# obc-v2_OUT-eMMC.net
KiCad netlist of a schematic drawn in Altium Designer
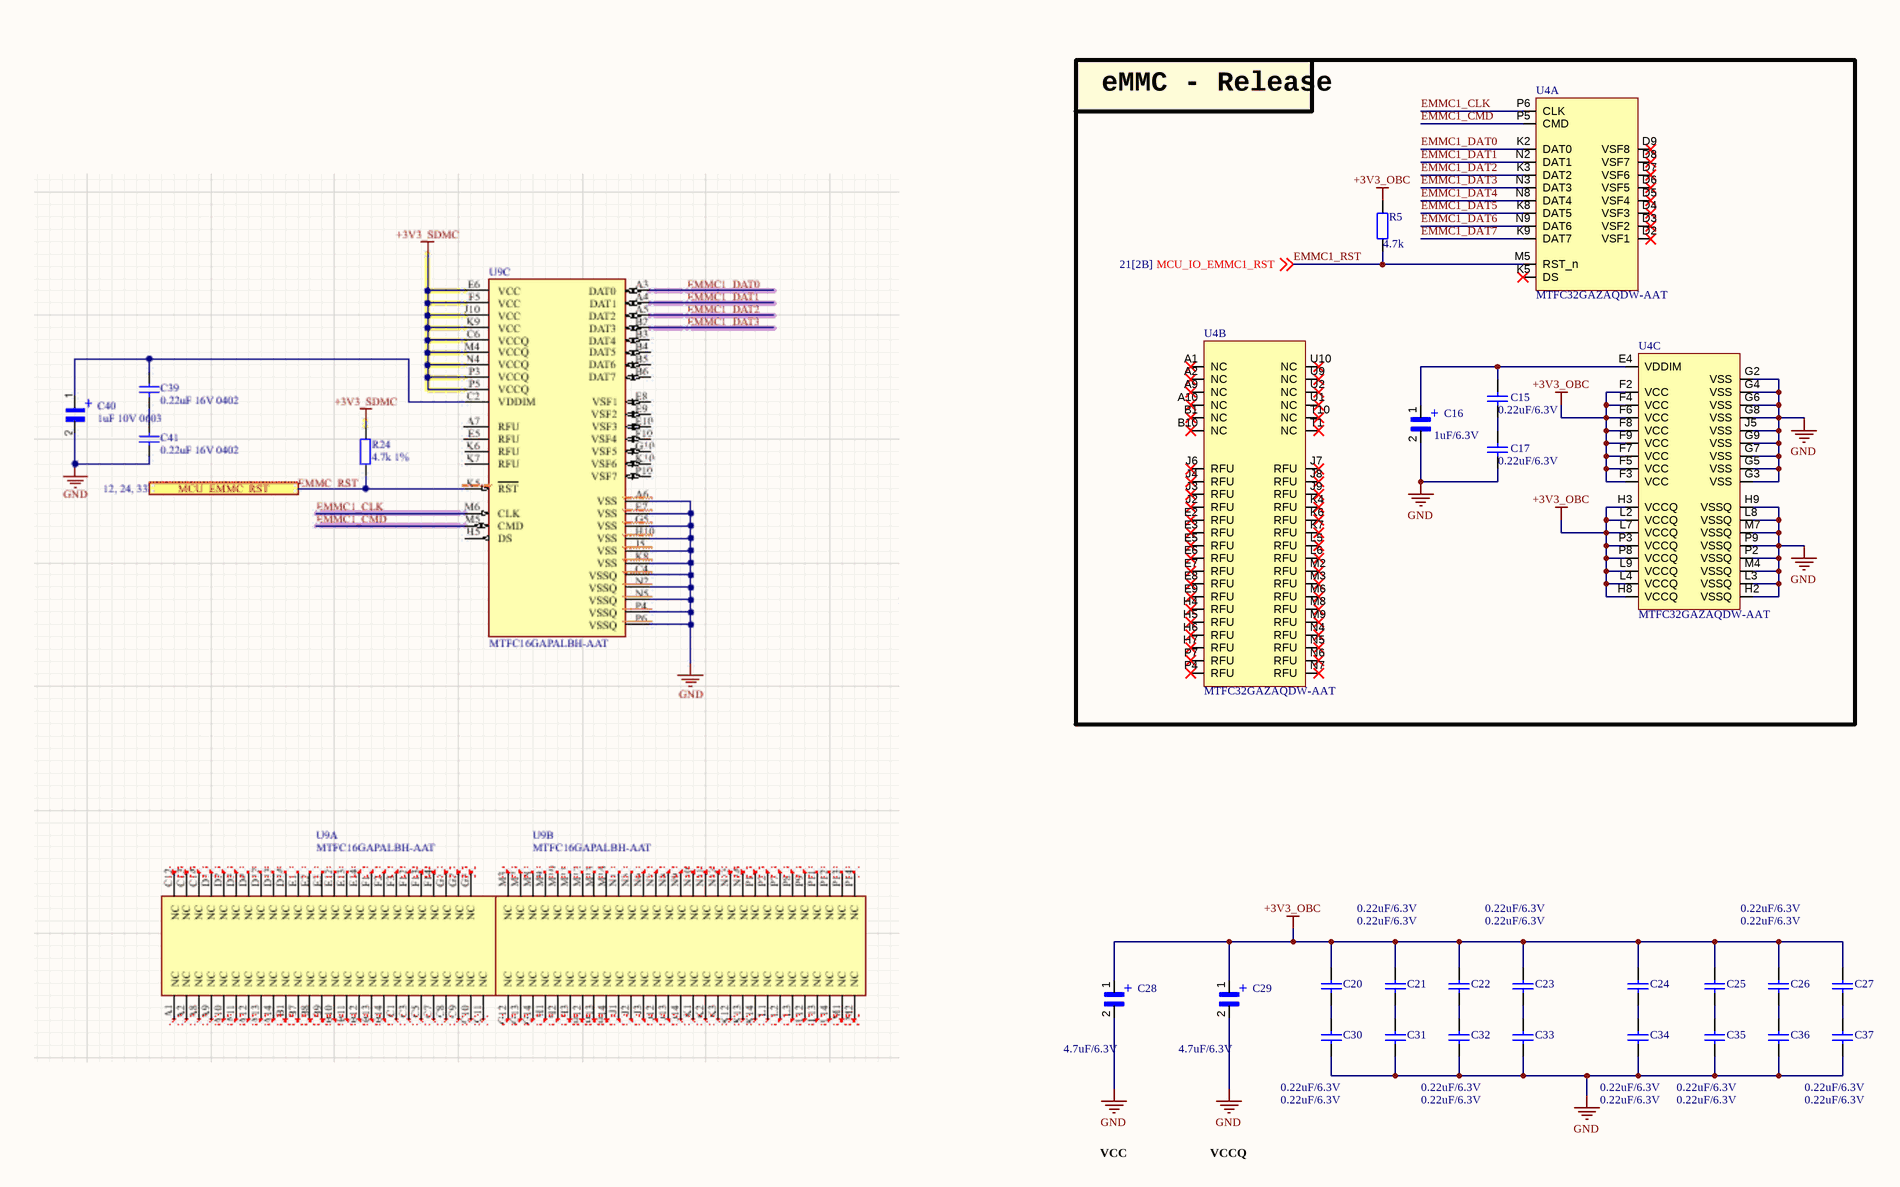
[diagram p0: obc-v2_OUT-eMMC.SchDoc, left]
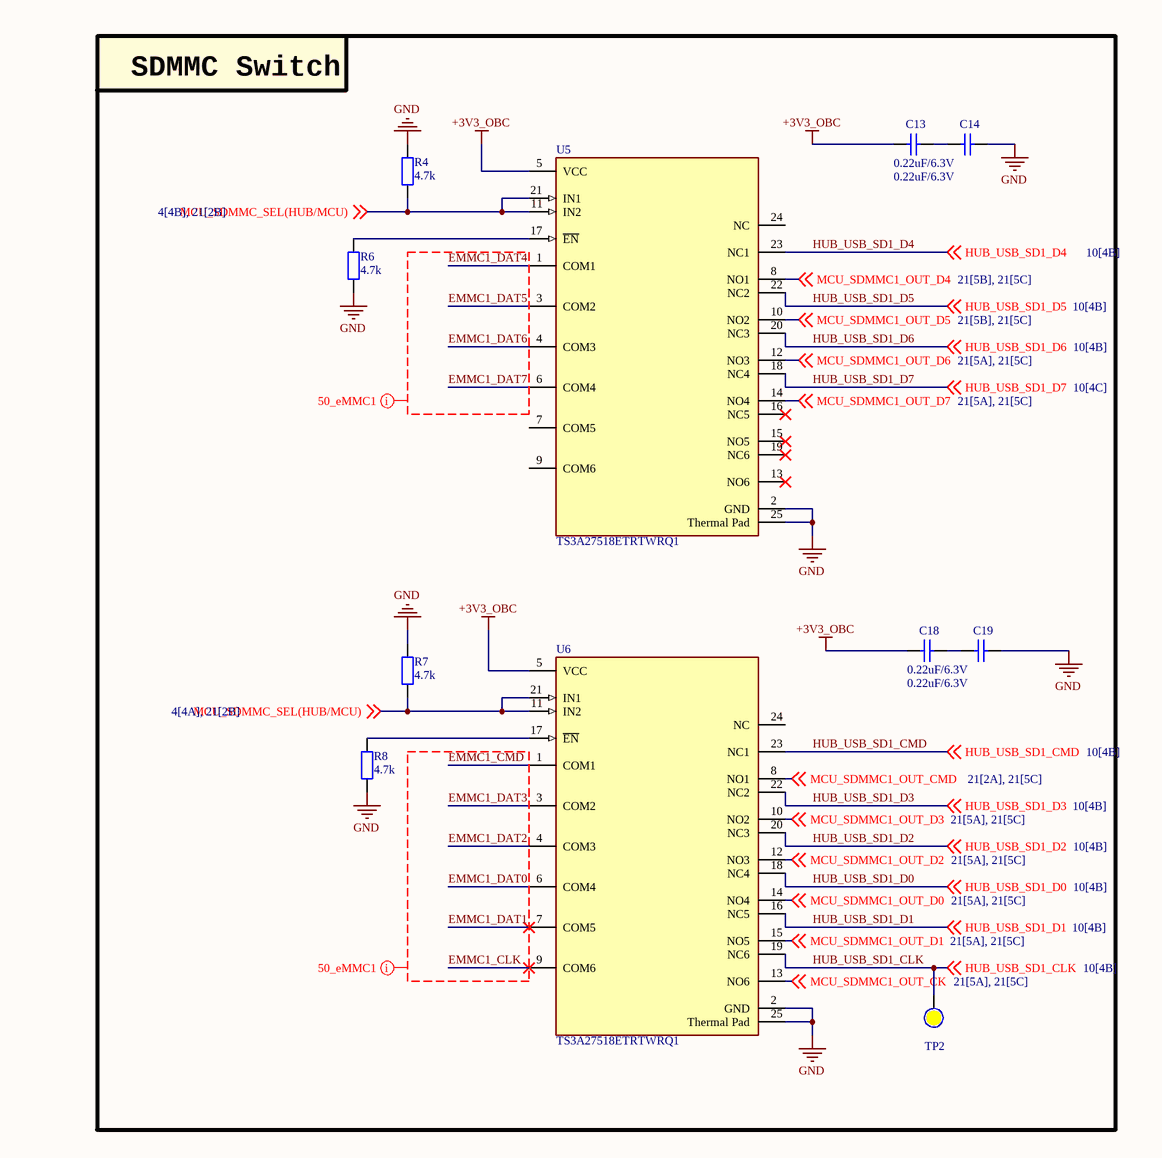
[diagram p1: obc-v2_OUT-eMMC.SchDoc, right]

(export (version "E")
  (design (tool "Eeschema 10.0.6"))
  (components
    (comp (ref "C13")
      (value "0.22uF/6.3V")
      (footprint "CAP_C_1005X60")
      (description "CAPC")
      (libsource (lib "Altium_Lib_by_KhueNguyenCreator") (part "Tu 0402 33nF 10V"))
    )
    (comp (ref "C14")
      (value "0.22uF/6.3V")
      (footprint "CAP_C_1005X60")
      (description "CAPC")
      (libsource (lib "Altium_Lib_by_KhueNguyenCreator") (part "Tu 0402 33nF 10V"))
    )
    (comp (ref "C15")
      (value "0.22uF/6.3V")
      (footprint "CAP_C_1005X60")
      (description "CAPC")
      (libsource (lib "Altium_Lib_by_KhueNguyenCreator") (part "Tu 0402 33nF 10V"))
    )
    (comp (ref "C16")
      (value "1uF/6.3V")
      (footprint "CAP_MP_1608X90")
      (description "CAPP")
      (fields (field (name "MP") "TACL335M003RTA"))
      (libsource (lib "TACL335M003RTA") (part "TACL335M003RTA"))
    )
    (comp (ref "C17")
      (value "0.22uF/6.3V")
      (footprint "CAP_C_1005X60")
      (description "CAPC")
      (libsource (lib "Altium_Lib_by_KhueNguyenCreator") (part "Tu 0402 33nF 10V"))
    )
    (comp (ref "C18")
      (value "0.22uF/6.3V")
      (footprint "CAP_C_1005X60")
      (description "CAPC")
      (libsource (lib "Altium_Lib_by_KhueNguyenCreator") (part "Tu 0402 33nF 10V"))
    )
    (comp (ref "C19")
      (value "0.22uF/6.3V")
      (footprint "CAP_C_1005X60")
      (description "CAPC")
      (libsource (lib "Altium_Lib_by_KhueNguyenCreator") (part "Tu 0402 33nF 10V"))
    )
    (comp (ref "C20")
      (value "0.22uF/6.3V")
      (footprint "CAP_C_1005X60")
      (description "CAPC")
      (libsource (lib "Altium_Lib_by_KhueNguyenCreator") (part "Tu 0402 33nF 10V"))
    )
    (comp (ref "C21")
      (value "0.22uF/6.3V")
      (footprint "CAP_C_1005X60")
      (description "CAPC")
      (libsource (lib "Altium_Lib_by_KhueNguyenCreator") (part "Tu 0402 33nF 10V"))
    )
    (comp (ref "C22")
      (value "0.22uF/6.3V")
      (footprint "CAP_C_1005X60")
      (description "CAPC")
      (libsource (lib "Altium_Lib_by_KhueNguyenCreator") (part "Tu 0402 33nF 10V"))
    )
    (comp (ref "C23")
      (value "0.22uF/6.3V")
      (footprint "CAP_C_1005X60")
      (description "CAPC")
      (libsource (lib "Altium_Lib_by_KhueNguyenCreator") (part "Tu 0402 33nF 10V"))
    )
    (comp (ref "C24")
      (value "0.22uF/6.3V")
      (footprint "CAP_C_1005X60")
      (description "CAPC")
      (libsource (lib "Altium_Lib_by_KhueNguyenCreator") (part "Tu 0402 33nF 10V"))
    )
    (comp (ref "C25")
      (value "0.22uF/6.3V")
      (footprint "CAP_C_1005X60")
      (description "CAPC")
      (libsource (lib "Altium_Lib_by_KhueNguyenCreator") (part "Tu 0402 33nF 10V"))
    )
    (comp (ref "C26")
      (value "0.22uF/6.3V")
      (footprint "CAP_C_1005X60")
      (description "CAPC")
      (libsource (lib "Altium_Lib_by_KhueNguyenCreator") (part "Tu 0402 33nF 10V"))
    )
    (comp (ref "C27")
      (value "0.22uF/6.3V")
      (footprint "CAP_C_1005X60")
      (description "CAPC")
      (libsource (lib "Altium_Lib_by_KhueNguyenCreator") (part "Tu 0402 33nF 10V"))
    )
    (comp (ref "C28")
      (value "4.7uF/6.3V")
      (footprint "CAP_MP_1608X90")
      (description "CAPP")
      (fields (field (name "MP") "TACL335M003RTA"))
      (libsource (lib "TACL335M003RTA") (part "TACL335M003RTA"))
    )
    (comp (ref "C29")
      (value "4.7uF/6.3V")
      (footprint "CAP_MP_1608X90")
      (description "CAPP")
      (fields (field (name "MP") "TACL335M003RTA"))
      (libsource (lib "TACL335M003RTA") (part "TACL335M003RTA"))
    )
    (comp (ref "C30")
      (value "0.22uF/6.3V")
      (footprint "CAP_C_1005X60")
      (description "CAPC")
      (libsource (lib "Altium_Lib_by_KhueNguyenCreator") (part "Tu 0402 33nF 10V"))
    )
    (comp (ref "C31")
      (value "0.22uF/6.3V")
      (footprint "CAP_C_1005X60")
      (description "CAPC")
      (libsource (lib "Altium_Lib_by_KhueNguyenCreator") (part "Tu 0402 33nF 10V"))
    )
    (comp (ref "C32")
      (value "0.22uF/6.3V")
      (footprint "CAP_C_1005X60")
      (description "CAPC")
      (libsource (lib "Altium_Lib_by_KhueNguyenCreator") (part "Tu 0402 33nF 10V"))
    )
    (comp (ref "C33")
      (value "0.22uF/6.3V")
      (footprint "CAP_C_1005X60")
      (description "CAPC")
      (libsource (lib "Altium_Lib_by_KhueNguyenCreator") (part "Tu 0402 33nF 10V"))
    )
    (comp (ref "C34")
      (value "0.22uF/6.3V")
      (footprint "CAP_C_1005X60")
      (description "CAPC")
      (libsource (lib "Altium_Lib_by_KhueNguyenCreator") (part "Tu 0402 33nF 10V"))
    )
    (comp (ref "C35")
      (value "0.22uF/6.3V")
      (footprint "CAP_C_1005X60")
      (description "CAPC")
      (libsource (lib "Altium_Lib_by_KhueNguyenCreator") (part "Tu 0402 33nF 10V"))
    )
    (comp (ref "C36")
      (value "0.22uF/6.3V")
      (footprint "CAP_C_1005X60")
      (description "CAPC")
      (libsource (lib "Altium_Lib_by_KhueNguyenCreator") (part "Tu 0402 33nF 10V"))
    )
    (comp (ref "C37")
      (value "0.22uF/6.3V")
      (footprint "CAP_C_1005X60")
      (description "CAPC")
      (libsource (lib "Altium_Lib_by_KhueNguyenCreator") (part "Tu 0402 33nF 10V"))
    )
    (comp (ref "R4")
      (value "4.7k")
      (footprint "RES_C_1608X60")
      (description "RES")
      (libsource (lib "Altium_Lib_by_KhueNguyenCreator") (part "Tro 0603 1% 10k"))
    )
    (comp (ref "R5")
      (value "4.7k")
      (footprint "RES_C_1608X60")
      (description "RES")
      (libsource (lib "Altium_Lib_by_KhueNguyenCreator") (part "Tro 0603 1% 10k"))
    )
    (comp (ref "R6")
      (value "4.7k")
      (footprint "RES_C_1608X60")
      (description "RES")
      (libsource (lib "Altium_Lib_by_KhueNguyenCreator") (part "Tro 0603 1% 10k"))
    )
    (comp (ref "R7")
      (value "4.7k")
      (footprint "RES_C_1608X60")
      (description "RES")
      (libsource (lib "Altium_Lib_by_KhueNguyenCreator") (part "Tro 0603 1% 10k"))
    )
    (comp (ref "R8")
      (value "4.7k")
      (footprint "RES_C_1608X60")
      (description "RES")
      (libsource (lib "Altium_Lib_by_KhueNguyenCreator") (part "Tro 0603 1% 10k"))
    )
    (comp (ref "TP2")
      (value "~")
      (footprint "Test Point 1 Side")
      (description "Test Point")
      (libsource (lib "BYTECH_HW_LIB_2019 (1)") (part "Test Point"))
    )
    (comp (ref "U4")
      (value "MTFC32GAZAQDW-AAT")
      (footprint "BGA_100_C_100P_10X17_1400X1800X150")
      (libsource (lib "emmc_nofootprint") (part "MTFC32GAZAQDW-AAT"))
    )
    (comp (ref "U5")
      (value "TS3A27518ETRTWRQ1")
      (footprint "FP-RTW0024B-IPC_A")
      (description "IC MUX/DEMUX 1X2 24WQFN")
      (libsource (lib "Altium Content Vault") (part "ff327f4631d6a819810aeca967572ba"))
    )
    (comp (ref "U6")
      (value "TS3A27518ETRTWRQ1")
      (footprint "FP-RTW0024B-IPC_A")
      (description "IC MUX/DEMUX 1X2 24WQFN")
      (libsource (lib "Altium Content Vault") (part "ff327f4631d6a819810aeca967572ba"))
    )
  )
  (nets
    (net (code "1") (name "+3V3_OBC") (class "Default")
      (node (ref "C13") (pin "2") (pinfunction "2_2") (pintype "passive"))
      (node (ref "C18") (pin "2") (pinfunction "2_2") (pintype "passive"))
      (node (ref "C20") (pin "1") (pinfunction "1_1") (pintype "passive"))
      (node (ref "C21") (pin "1") (pinfunction "1_1") (pintype "passive"))
      (node (ref "C22") (pin "1") (pinfunction "1_1") (pintype "passive"))
      (node (ref "C23") (pin "1") (pinfunction "1_1") (pintype "passive"))
      (node (ref "C24") (pin "1") (pinfunction "1_1") (pintype "passive"))
      (node (ref "C25") (pin "1") (pinfunction "1_1") (pintype "passive"))
      (node (ref "C26") (pin "1") (pinfunction "1_1") (pintype "passive"))
      (node (ref "C27") (pin "1") (pinfunction "1_1") (pintype "passive"))
      (node (ref "C28") (pin "1") (pinfunction "1_1") (pintype "passive"))
      (node (ref "C29") (pin "1") (pinfunction "1_1") (pintype "passive"))
      (node (ref "R5") (pin "1") (pinfunction "1_1") (pintype "passive"))
      (node (ref "U4") (pin "F2") (pinfunction "VCC_F2") (pintype "passive"))
      (node (ref "U4") (pin "F3") (pinfunction "VCC_F3") (pintype "passive"))
      (node (ref "U4") (pin "F4") (pinfunction "VCC_F4") (pintype "passive"))
      (node (ref "U4") (pin "F5") (pinfunction "VCC_F5") (pintype "passive"))
      (node (ref "U4") (pin "F6") (pinfunction "VCC_F6") (pintype "passive"))
      (node (ref "U4") (pin "F7") (pinfunction "VCC_F7") (pintype "passive"))
      (node (ref "U4") (pin "F8") (pinfunction "VCC_F8") (pintype "passive"))
      (node (ref "U4") (pin "F9") (pinfunction "VCC_F9") (pintype "passive"))
      (node (ref "U4") (pin "H3") (pinfunction "VCCQ_H3") (pintype "passive"))
      (node (ref "U4") (pin "H8") (pinfunction "VCCQ_H8") (pintype "passive"))
      (node (ref "U4") (pin "L2") (pinfunction "VCCQ_L2") (pintype "passive"))
      (node (ref "U4") (pin "L4") (pinfunction "VCCQ_L4") (pintype "passive"))
      (node (ref "U4") (pin "L7") (pinfunction "VCCQ_L7") (pintype "passive"))
      (node (ref "U4") (pin "L9") (pinfunction "VCCQ_L9") (pintype "passive"))
      (node (ref "U4") (pin "P3") (pinfunction "VCCQ_P3") (pintype "passive"))
      (node (ref "U4") (pin "P8") (pinfunction "VCCQ_P8") (pintype "passive"))
      (node (ref "U5") (pin "5") (pinfunction "VCC_5") (pintype "power_in"))
      (node (ref "U6") (pin "5") (pinfunction "VCC_5") (pintype "power_in"))
    )
    (net (code "2") (name "/EMMC1_CLK") (class "Default")
      (node (ref "U4") (pin "P6") (pinfunction "CLK_P6") (pintype "passive"))
      (node (ref "U6") (pin "9") (pinfunction "COM6_9") (pintype "passive"))
    )
    (net (code "3") (name "/EMMC1_CMD") (class "Default")
      (node (ref "U4") (pin "P5") (pinfunction "CMD_P5") (pintype "passive"))
      (node (ref "U6") (pin "1") (pinfunction "COM1_1") (pintype "passive"))
    )
    (net (code "4") (name "/EMMC1_DAT0") (class "Default")
      (node (ref "U4") (pin "K2") (pinfunction "DAT0_K2") (pintype "passive"))
      (node (ref "U6") (pin "6") (pinfunction "COM4_6") (pintype "passive"))
    )
    (net (code "5") (name "/EMMC1_DAT1") (class "Default")
      (node (ref "U4") (pin "N2") (pinfunction "DAT1_N2") (pintype "passive"))
      (node (ref "U6") (pin "7") (pinfunction "COM5_7") (pintype "passive"))
    )
    (net (code "6") (name "/EMMC1_DAT2") (class "Default")
      (node (ref "U4") (pin "K3") (pinfunction "DAT2_K3") (pintype "passive"))
      (node (ref "U6") (pin "4") (pinfunction "COM3_4") (pintype "passive"))
    )
    (net (code "7") (name "/EMMC1_DAT3") (class "Default")
      (node (ref "U4") (pin "N3") (pinfunction "DAT3_N3") (pintype "passive"))
      (node (ref "U6") (pin "3") (pinfunction "COM2_3") (pintype "passive"))
    )
    (net (code "8") (name "/EMMC1_DAT4") (class "Default")
      (node (ref "U4") (pin "N8") (pinfunction "DAT4_N8") (pintype "passive"))
      (node (ref "U5") (pin "1") (pinfunction "COM1_1") (pintype "passive"))
    )
    (net (code "9") (name "/EMMC1_DAT5") (class "Default")
      (node (ref "U4") (pin "K8") (pinfunction "DAT5_K8") (pintype "passive"))
      (node (ref "U5") (pin "3") (pinfunction "COM2_3") (pintype "passive"))
    )
    (net (code "10") (name "/EMMC1_DAT6") (class "Default")
      (node (ref "U4") (pin "N9") (pinfunction "DAT6_N9") (pintype "passive"))
      (node (ref "U5") (pin "4") (pinfunction "COM3_4") (pintype "passive"))
    )
    (net (code "11") (name "/EMMC1_DAT7") (class "Default")
      (node (ref "U4") (pin "K9") (pinfunction "DAT7_K9") (pintype "passive"))
      (node (ref "U5") (pin "6") (pinfunction "COM4_6") (pintype "passive"))
    )
    (net (code "12") (name "GND") (class "Default")
      (node (ref "C14") (pin "1") (pinfunction "1_1") (pintype "passive"))
      (node (ref "C16") (pin "2") (pinfunction "2_2") (pintype "passive"))
      (node (ref "C17") (pin "2") (pinfunction "2_2") (pintype "passive"))
      (node (ref "C19") (pin "1") (pinfunction "1_1") (pintype "passive"))
      (node (ref "C28") (pin "2") (pinfunction "2_2") (pintype "passive"))
      (node (ref "C29") (pin "2") (pinfunction "2_2") (pintype "passive"))
      (node (ref "C30") (pin "2") (pinfunction "2_2") (pintype "passive"))
      (node (ref "C31") (pin "2") (pinfunction "2_2") (pintype "passive"))
      (node (ref "C32") (pin "2") (pinfunction "2_2") (pintype "passive"))
      (node (ref "C33") (pin "2") (pinfunction "2_2") (pintype "passive"))
      (node (ref "C34") (pin "2") (pinfunction "2_2") (pintype "passive"))
      (node (ref "C35") (pin "2") (pinfunction "2_2") (pintype "passive"))
      (node (ref "C36") (pin "2") (pinfunction "2_2") (pintype "passive"))
      (node (ref "C37") (pin "2") (pinfunction "2_2") (pintype "passive"))
      (node (ref "R4") (pin "1") (pinfunction "1_1") (pintype "passive"))
      (node (ref "R6") (pin "2") (pinfunction "2_2") (pintype "passive"))
      (node (ref "R7") (pin "1") (pinfunction "1_1") (pintype "passive"))
      (node (ref "R8") (pin "2") (pinfunction "2_2") (pintype "passive"))
      (node (ref "U4") (pin "G2") (pinfunction "VSS_G2") (pintype "passive"))
      (node (ref "U4") (pin "G3") (pinfunction "VSS_G3") (pintype "passive"))
      (node (ref "U4") (pin "G4") (pinfunction "VSS_G4") (pintype "passive"))
      (node (ref "U4") (pin "G5") (pinfunction "VSS_G5") (pintype "passive"))
      (node (ref "U4") (pin "G6") (pinfunction "VSS_G6") (pintype "passive"))
      (node (ref "U4") (pin "G7") (pinfunction "VSS_G7") (pintype "passive"))
      (node (ref "U4") (pin "G8") (pinfunction "VSS_G8") (pintype "passive"))
      (node (ref "U4") (pin "G9") (pinfunction "VSS_G9") (pintype "passive"))
      (node (ref "U4") (pin "H2") (pinfunction "VSSQ_H2") (pintype "passive"))
      (node (ref "U4") (pin "H9") (pinfunction "VSSQ_H9") (pintype "passive"))
      (node (ref "U4") (pin "J5") (pinfunction "VSS_J5") (pintype "passive"))
      (node (ref "U4") (pin "L3") (pinfunction "VSSQ_L3") (pintype "passive"))
      (node (ref "U4") (pin "L8") (pinfunction "VSSQ_L8") (pintype "passive"))
      (node (ref "U4") (pin "M4") (pinfunction "VSSQ_M4") (pintype "passive"))
      (node (ref "U4") (pin "M7") (pinfunction "VSSQ_M7") (pintype "passive"))
      (node (ref "U4") (pin "P2") (pinfunction "VSSQ_P2") (pintype "passive"))
      (node (ref "U4") (pin "P9") (pinfunction "VSSQ_P9") (pintype "passive"))
      (node (ref "U5") (pin "2") (pinfunction "GND_2") (pintype "power_in"))
      (node (ref "U5") (pin "25") (pinfunction "Thermal_Pad_25") (pintype "power_in"))
      (node (ref "U6") (pin "2") (pinfunction "GND_2") (pintype "power_in"))
      (node (ref "U6") (pin "25") (pinfunction "Thermal_Pad_25") (pintype "power_in"))
    )
    (net (code "13") (name "HUB_USB_SD1_CLK") (class "Default")
      (node (ref "TP2") (pin "0") (pinfunction "0_0") (pintype "passive"))
      (node (ref "U6") (pin "19") (pinfunction "NC6_19") (pintype "passive"))
    )
    (net (code "14") (name "HUB_USB_SD1_CMD") (class "Default")
      (node (ref "U6") (pin "23") (pinfunction "NC1_23") (pintype "passive"))
    )
    (net (code "15") (name "HUB_USB_SD1_D0") (class "Default")
      (node (ref "U6") (pin "18") (pinfunction "NC4_18") (pintype "passive"))
    )
    (net (code "16") (name "HUB_USB_SD1_D1") (class "Default")
      (node (ref "U6") (pin "16") (pinfunction "NC5_16") (pintype "passive"))
    )
    (net (code "17") (name "HUB_USB_SD1_D2") (class "Default")
      (node (ref "U6") (pin "20") (pinfunction "NC3_20") (pintype "passive"))
    )
    (net (code "18") (name "HUB_USB_SD1_D3") (class "Default")
      (node (ref "U6") (pin "22") (pinfunction "NC2_22") (pintype "passive"))
    )
    (net (code "19") (name "HUB_USB_SD1_D4") (class "Default")
      (node (ref "U5") (pin "23") (pinfunction "NC1_23") (pintype "passive"))
    )
    (net (code "20") (name "HUB_USB_SD1_D5") (class "Default")
      (node (ref "U5") (pin "22") (pinfunction "NC2_22") (pintype "passive"))
    )
    (net (code "21") (name "HUB_USB_SD1_D6") (class "Default")
      (node (ref "U5") (pin "20") (pinfunction "NC3_20") (pintype "passive"))
    )
    (net (code "22") (name "HUB_USB_SD1_D7") (class "Default")
      (node (ref "U5") (pin "18") (pinfunction "NC4_18") (pintype "passive"))
    )
    (net (code "23") (name "MCU_IO_EMMC1_RST") (class "Default")
      (node (ref "R5") (pin "2") (pinfunction "2_2") (pintype "passive"))
      (node (ref "U4") (pin "M5") (pinfunction "RST_n_M5") (pintype "passive"))
    )
    (net (code "24") (name "MCU_SDMMC1_OUT_CK") (class "Default")
      (node (ref "U6") (pin "13") (pinfunction "NO6_13") (pintype "passive"))
    )
    (net (code "25") (name "MCU_SDMMC1_OUT_CMD") (class "Default")
      (node (ref "U6") (pin "8") (pinfunction "NO1_8") (pintype "passive"))
    )
    (net (code "26") (name "MCU_SDMMC1_OUT_D0") (class "Default")
      (node (ref "U6") (pin "14") (pinfunction "NO4_14") (pintype "passive"))
    )
    (net (code "27") (name "MCU_SDMMC1_OUT_D1") (class "Default")
      (node (ref "U6") (pin "15") (pinfunction "NO5_15") (pintype "passive"))
    )
    (net (code "28") (name "MCU_SDMMC1_OUT_D2") (class "Default")
      (node (ref "U6") (pin "12") (pinfunction "NO3_12") (pintype "passive"))
    )
    (net (code "29") (name "MCU_SDMMC1_OUT_D3") (class "Default")
      (node (ref "U6") (pin "10") (pinfunction "NO2_10") (pintype "passive"))
    )
    (net (code "30") (name "MCU_SDMMC1_OUT_D4") (class "Default")
      (node (ref "U5") (pin "8") (pinfunction "NO1_8") (pintype "passive"))
    )
    (net (code "31") (name "MCU_SDMMC1_OUT_D5") (class "Default")
      (node (ref "U5") (pin "10") (pinfunction "NO2_10") (pintype "passive"))
    )
    (net (code "32") (name "MCU_SDMMC1_OUT_D6") (class "Default")
      (node (ref "U5") (pin "12") (pinfunction "NO3_12") (pintype "passive"))
    )
    (net (code "33") (name "MCU_SDMMC1_OUT_D7") (class "Default")
      (node (ref "U5") (pin "14") (pinfunction "NO4_14") (pintype "passive"))
    )
    (net (code "34") (name "MCU_SDMMC_SEL(HUB{slash}MCU)") (class "Default")
      (node (ref "R4") (pin "2") (pinfunction "2_2") (pintype "passive"))
      (node (ref "R7") (pin "2") (pinfunction "2_2") (pintype "passive"))
      (node (ref "U5") (pin "11") (pinfunction "IN2_11") (pintype "input"))
      (node (ref "U5") (pin "21") (pinfunction "IN1_21") (pintype "input"))
      (node (ref "U6") (pin "11") (pinfunction "IN2_11") (pintype "input"))
      (node (ref "U6") (pin "21") (pinfunction "IN1_21") (pintype "input"))
    )
    (net (code "35") (name "Net-(C13-Pad1)") (class "Default")
      (node (ref "C13") (pin "1") (pinfunction "1_1") (pintype "passive"))
      (node (ref "C14") (pin "2") (pinfunction "2_2") (pintype "passive"))
    )
    (net (code "36") (name "Net-(C15-Pad2)") (class "Default")
      (node (ref "C15") (pin "2") (pinfunction "2_2") (pintype "passive"))
      (node (ref "C17") (pin "1") (pinfunction "1_1") (pintype "passive"))
    )
    (net (code "37") (name "Net-(C18-Pad1)") (class "Default")
      (node (ref "C18") (pin "1") (pinfunction "1_1") (pintype "passive"))
      (node (ref "C19") (pin "2") (pinfunction "2_2") (pintype "passive"))
    )
    (net (code "38") (name "Net-(C20-Pad2)") (class "Default")
      (node (ref "C20") (pin "2") (pinfunction "2_2") (pintype "passive"))
      (node (ref "C30") (pin "1") (pinfunction "1_1") (pintype "passive"))
    )
    (net (code "39") (name "Net-(C21-Pad2)") (class "Default")
      (node (ref "C21") (pin "2") (pinfunction "2_2") (pintype "passive"))
      (node (ref "C31") (pin "1") (pinfunction "1_1") (pintype "passive"))
    )
    (net (code "40") (name "Net-(C22-Pad2)") (class "Default")
      (node (ref "C22") (pin "2") (pinfunction "2_2") (pintype "passive"))
      (node (ref "C32") (pin "1") (pinfunction "1_1") (pintype "passive"))
    )
    (net (code "41") (name "Net-(C23-Pad2)") (class "Default")
      (node (ref "C23") (pin "2") (pinfunction "2_2") (pintype "passive"))
      (node (ref "C33") (pin "1") (pinfunction "1_1") (pintype "passive"))
    )
    (net (code "42") (name "Net-(C24-Pad2)") (class "Default")
      (node (ref "C24") (pin "2") (pinfunction "2_2") (pintype "passive"))
      (node (ref "C34") (pin "1") (pinfunction "1_1") (pintype "passive"))
    )
    (net (code "43") (name "Net-(C25-Pad2)") (class "Default")
      (node (ref "C25") (pin "2") (pinfunction "2_2") (pintype "passive"))
      (node (ref "C35") (pin "1") (pinfunction "1_1") (pintype "passive"))
    )
    (net (code "44") (name "Net-(C26-Pad2)") (class "Default")
      (node (ref "C26") (pin "2") (pinfunction "2_2") (pintype "passive"))
      (node (ref "C36") (pin "1") (pinfunction "1_1") (pintype "passive"))
    )
    (net (code "45") (name "Net-(C27-Pad2)") (class "Default")
      (node (ref "C27") (pin "2") (pinfunction "2_2") (pintype "passive"))
      (node (ref "C37") (pin "1") (pinfunction "1_1") (pintype "passive"))
    )
    (net (code "46") (name "Net-(U4C-VDDIM)") (class "Default")
      (node (ref "C15") (pin "1") (pinfunction "1_1") (pintype "passive"))
      (node (ref "C16") (pin "1") (pinfunction "1_1") (pintype "passive"))
      (node (ref "U4") (pin "E4") (pinfunction "VDDIM_E4") (pintype "passive"))
    )
    (net (code "47") (name "Net-(U5-~{EN})") (class "Default")
      (node (ref "R6") (pin "1") (pinfunction "1_1") (pintype "passive"))
      (node (ref "U5") (pin "17") (pinfunction "~{EN}_17") (pintype "input"))
    )
    (net (code "48") (name "Net-(U6-~{EN})") (class "Default")
      (node (ref "R8") (pin "1") (pinfunction "1_1") (pintype "passive"))
      (node (ref "U6") (pin "17") (pinfunction "~{EN}_17") (pintype "input"))
    )
    (net (code "49") (name "unconnected-(U4A-DS-PadK5)") (class "Default")
      (node (ref "U4") (pin "K5") (pinfunction "DS_K5") (pintype "passive+no_connect"))
    )
    (net (code "50") (name "unconnected-(U4A-VSF1-PadD2)") (class "Default")
      (node (ref "U4") (pin "D2") (pinfunction "VSF1_D2") (pintype "passive+no_connect"))
    )
    (net (code "51") (name "unconnected-(U4A-VSF2-PadD3)") (class "Default")
      (node (ref "U4") (pin "D3") (pinfunction "VSF2_D3") (pintype "passive+no_connect"))
    )
    (net (code "52") (name "unconnected-(U4A-VSF3-PadD4)") (class "Default")
      (node (ref "U4") (pin "D4") (pinfunction "VSF3_D4") (pintype "passive+no_connect"))
    )
    (net (code "53") (name "unconnected-(U4A-VSF4-PadD5)") (class "Default")
      (node (ref "U4") (pin "D5") (pinfunction "VSF4_D5") (pintype "passive+no_connect"))
    )
    (net (code "54") (name "unconnected-(U4A-VSF5-PadD6)") (class "Default")
      (node (ref "U4") (pin "D6") (pinfunction "VSF5_D6") (pintype "passive+no_connect"))
    )
    (net (code "55") (name "unconnected-(U4A-VSF6-PadD7)") (class "Default")
      (node (ref "U4") (pin "D7") (pinfunction "VSF6_D7") (pintype "passive+no_connect"))
    )
    (net (code "56") (name "unconnected-(U4A-VSF7-PadD8)") (class "Default")
      (node (ref "U4") (pin "D8") (pinfunction "VSF7_D8") (pintype "passive+no_connect"))
    )
    (net (code "57") (name "unconnected-(U4A-VSF8-PadD9)") (class "Default")
      (node (ref "U4") (pin "D9") (pinfunction "VSF8_D9") (pintype "passive+no_connect"))
    )
    (net (code "58") (name "unconnected-(U4B-NC-PadA1)") (class "Default")
      (node (ref "U4") (pin "A1") (pinfunction "NC_A1") (pintype "passive+no_connect"))
    )
    (net (code "59") (name "unconnected-(U4B-NC-PadA2)") (class "Default")
      (node (ref "U4") (pin "A2") (pinfunction "NC_A2") (pintype "passive+no_connect"))
    )
    (net (code "60") (name "unconnected-(U4B-NC-PadA9)") (class "Default")
      (node (ref "U4") (pin "A9") (pinfunction "NC_A9") (pintype "passive+no_connect"))
    )
    (net (code "61") (name "unconnected-(U4B-NC-PadA10)") (class "Default")
      (node (ref "U4") (pin "A10") (pinfunction "NC_A10") (pintype "passive+no_connect"))
    )
    (net (code "62") (name "unconnected-(U4B-NC-PadB1)") (class "Default")
      (node (ref "U4") (pin "B1") (pinfunction "NC_B1") (pintype "passive+no_connect"))
    )
    (net (code "63") (name "unconnected-(U4B-NC-PadB10)") (class "Default")
      (node (ref "U4") (pin "B10") (pinfunction "NC_B10") (pintype "passive+no_connect"))
    )
    (net (code "64") (name "unconnected-(U4B-NC-PadT1)") (class "Default")
      (node (ref "U4") (pin "T1") (pinfunction "NC_T1") (pintype "passive+no_connect"))
    )
    (net (code "65") (name "unconnected-(U4B-NC-PadT10)") (class "Default")
      (node (ref "U4") (pin "T10") (pinfunction "NC_T10") (pintype "passive+no_connect"))
    )
    (net (code "66") (name "unconnected-(U4B-NC-PadU1)") (class "Default")
      (node (ref "U4") (pin "U1") (pinfunction "NC_U1") (pintype "passive+no_connect"))
    )
    (net (code "67") (name "unconnected-(U4B-NC-PadU2)") (class "Default")
      (node (ref "U4") (pin "U2") (pinfunction "NC_U2") (pintype "passive+no_connect"))
    )
    (net (code "68") (name "unconnected-(U4B-NC-PadU9)") (class "Default")
      (node (ref "U4") (pin "U9") (pinfunction "NC_U9") (pintype "passive+no_connect"))
    )
    (net (code "69") (name "unconnected-(U4B-NC-PadU10)") (class "Default")
      (node (ref "U4") (pin "U10") (pinfunction "NC_U10") (pintype "passive+no_connect"))
    )
    (net (code "70") (name "unconnected-(U4B-RFU-PadE2)") (class "Default")
      (node (ref "U4") (pin "E2") (pinfunction "RFU_E2") (pintype "passive+no_connect"))
    )
    (net (code "71") (name "unconnected-(U4B-RFU-PadE3)") (class "Default")
      (node (ref "U4") (pin "E3") (pinfunction "RFU_E3") (pintype "passive+no_connect"))
    )
    (net (code "72") (name "unconnected-(U4B-RFU-PadE5)") (class "Default")
      (node (ref "U4") (pin "E5") (pinfunction "RFU_E5") (pintype "passive+no_connect"))
    )
    (net (code "73") (name "unconnected-(U4B-RFU-PadE6)") (class "Default")
      (node (ref "U4") (pin "E6") (pinfunction "RFU_E6") (pintype "passive+no_connect"))
    )
    (net (code "74") (name "unconnected-(U4B-RFU-PadE7)") (class "Default")
      (node (ref "U4") (pin "E7") (pinfunction "RFU_E7") (pintype "passive+no_connect"))
    )
    (net (code "75") (name "unconnected-(U4B-RFU-PadE8)") (class "Default")
      (node (ref "U4") (pin "E8") (pinfunction "RFU_E8") (pintype "passive+no_connect"))
    )
    (net (code "76") (name "unconnected-(U4B-RFU-PadE9)") (class "Default")
      (node (ref "U4") (pin "E9") (pinfunction "RFU_E9") (pintype "passive+no_connect"))
    )
    (net (code "77") (name "unconnected-(U4B-RFU-PadH4)") (class "Default")
      (node (ref "U4") (pin "H4") (pinfunction "RFU_H4") (pintype "passive+no_connect"))
    )
    (net (code "78") (name "unconnected-(U4B-RFU-PadH5)") (class "Default")
      (node (ref "U4") (pin "H5") (pinfunction "RFU_H5") (pintype "passive+no_connect"))
    )
    (net (code "79") (name "unconnected-(U4B-RFU-PadH6)") (class "Default")
      (node (ref "U4") (pin "H6") (pinfunction "RFU_H6") (pintype "passive+no_connect"))
    )
    (net (code "80") (name "unconnected-(U4B-RFU-PadH7)") (class "Default")
      (node (ref "U4") (pin "H7") (pinfunction "RFU_H7") (pintype "passive+no_connect"))
    )
    (net (code "81") (name "unconnected-(U4B-RFU-PadJ2)") (class "Default")
      (node (ref "U4") (pin "J2") (pinfunction "RFU_J2") (pintype "passive+no_connect"))
    )
    (net (code "82") (name "unconnected-(U4B-RFU-PadJ3)") (class "Default")
      (node (ref "U4") (pin "J3") (pinfunction "RFU_J3") (pintype "passive+no_connect"))
    )
    (net (code "83") (name "unconnected-(U4B-RFU-PadJ4)") (class "Default")
      (node (ref "U4") (pin "J4") (pinfunction "RFU_J4") (pintype "passive+no_connect"))
    )
    (net (code "84") (name "unconnected-(U4B-RFU-PadJ6)") (class "Default")
      (node (ref "U4") (pin "J6") (pinfunction "RFU_J6") (pintype "passive+no_connect"))
    )
    (net (code "85") (name "unconnected-(U4B-RFU-PadJ7)") (class "Default")
      (node (ref "U4") (pin "J7") (pinfunction "RFU_J7") (pintype "passive+no_connect"))
    )
    (net (code "86") (name "unconnected-(U4B-RFU-PadJ8)") (class "Default")
      (node (ref "U4") (pin "J8") (pinfunction "RFU_J8") (pintype "passive+no_connect"))
    )
    (net (code "87") (name "unconnected-(U4B-RFU-PadJ9)") (class "Default")
      (node (ref "U4") (pin "J9") (pinfunction "RFU_J9") (pintype "passive+no_connect"))
    )
    (net (code "88") (name "unconnected-(U4B-RFU-PadK4)") (class "Default")
      (node (ref "U4") (pin "K4") (pinfunction "RFU_K4") (pintype "passive+no_connect"))
    )
    (net (code "89") (name "unconnected-(U4B-RFU-PadK6)") (class "Default")
      (node (ref "U4") (pin "K6") (pinfunction "RFU_K6") (pintype "passive+no_connect"))
    )
    (net (code "90") (name "unconnected-(U4B-RFU-PadK7)") (class "Default")
      (node (ref "U4") (pin "K7") (pinfunction "RFU_K7") (pintype "passive+no_connect"))
    )
    (net (code "91") (name "unconnected-(U4B-RFU-PadL5)") (class "Default")
      (node (ref "U4") (pin "L5") (pinfunction "RFU_L5") (pintype "passive+no_connect"))
    )
    (net (code "92") (name "unconnected-(U4B-RFU-PadL6)") (class "Default")
      (node (ref "U4") (pin "L6") (pinfunction "RFU_L6") (pintype "passive+no_connect"))
    )
    (net (code "93") (name "unconnected-(U4B-RFU-PadM2)") (class "Default")
      (node (ref "U4") (pin "M2") (pinfunction "RFU_M2") (pintype "passive+no_connect"))
    )
    (net (code "94") (name "unconnected-(U4B-RFU-PadM3)") (class "Default")
      (node (ref "U4") (pin "M3") (pinfunction "RFU_M3") (pintype "passive+no_connect"))
    )
    (net (code "95") (name "unconnected-(U4B-RFU-PadM6)") (class "Default")
      (node (ref "U4") (pin "M6") (pinfunction "RFU_M6") (pintype "passive+no_connect"))
    )
    (net (code "96") (name "unconnected-(U4B-RFU-PadM8)") (class "Default")
      (node (ref "U4") (pin "M8") (pinfunction "RFU_M8") (pintype "passive+no_connect"))
    )
    (net (code "97") (name "unconnected-(U4B-RFU-PadM9)") (class "Default")
      (node (ref "U4") (pin "M9") (pinfunction "RFU_M9") (pintype "passive+no_connect"))
    )
    (net (code "98") (name "unconnected-(U4B-RFU-PadN4)") (class "Default")
      (node (ref "U4") (pin "N4") (pinfunction "RFU_N4") (pintype "passive+no_connect"))
    )
    (net (code "99") (name "unconnected-(U4B-RFU-PadN5)") (class "Default")
      (node (ref "U4") (pin "N5") (pinfunction "RFU_N5") (pintype "passive+no_connect"))
    )
    (net (code "100") (name "unconnected-(U4B-RFU-PadN6)") (class "Default")
      (node (ref "U4") (pin "N6") (pinfunction "RFU_N6") (pintype "passive+no_connect"))
    )
    (net (code "101") (name "unconnected-(U4B-RFU-PadN7)") (class "Default")
      (node (ref "U4") (pin "N7") (pinfunction "RFU_N7") (pintype "passive+no_connect"))
    )
    (net (code "102") (name "unconnected-(U4B-RFU-PadP4)") (class "Default")
      (node (ref "U4") (pin "P4") (pinfunction "RFU_P4") (pintype "passive+no_connect"))
    )
    (net (code "103") (name "unconnected-(U4B-RFU-PadP7)") (class "Default")
      (node (ref "U4") (pin "P7") (pinfunction "RFU_P7") (pintype "passive+no_connect"))
    )
    (net (code "104") (name "unconnected-(U5-COM5-Pad7)") (class "Default")
      (node (ref "U5") (pin "7") (pinfunction "COM5_7") (pintype "passive"))
    )
    (net (code "105") (name "unconnected-(U5-COM6-Pad9)") (class "Default")
      (node (ref "U5") (pin "9") (pinfunction "COM6_9") (pintype "passive"))
    )
    (net (code "106") (name "unconnected-(U5-NC-Pad24)") (class "Default")
      (node (ref "U5") (pin "24") (pinfunction "NC_24") (pintype "passive"))
    )
    (net (code "107") (name "unconnected-(U5-NC5-Pad16)") (class "Default")
      (node (ref "U5") (pin "16") (pinfunction "NC5_16") (pintype "passive+no_connect"))
    )
    (net (code "108") (name "unconnected-(U5-NC6-Pad19)") (class "Default")
      (node (ref "U5") (pin "19") (pinfunction "NC6_19") (pintype "passive+no_connect"))
    )
    (net (code "109") (name "unconnected-(U5-NO5-Pad15)") (class "Default")
      (node (ref "U5") (pin "15") (pinfunction "NO5_15") (pintype "passive+no_connect"))
    )
    (net (code "110") (name "unconnected-(U5-NO6-Pad13)") (class "Default")
      (node (ref "U5") (pin "13") (pinfunction "NO6_13") (pintype "passive+no_connect"))
    )
    (net (code "111") (name "unconnected-(U6-NC-Pad24)") (class "Default")
      (node (ref "U6") (pin "24") (pinfunction "NC_24") (pintype "passive"))
    )
  )
)
